# DM1092_TopLevel.net
KiCad netlist of a schematic drawn in Altium Designer
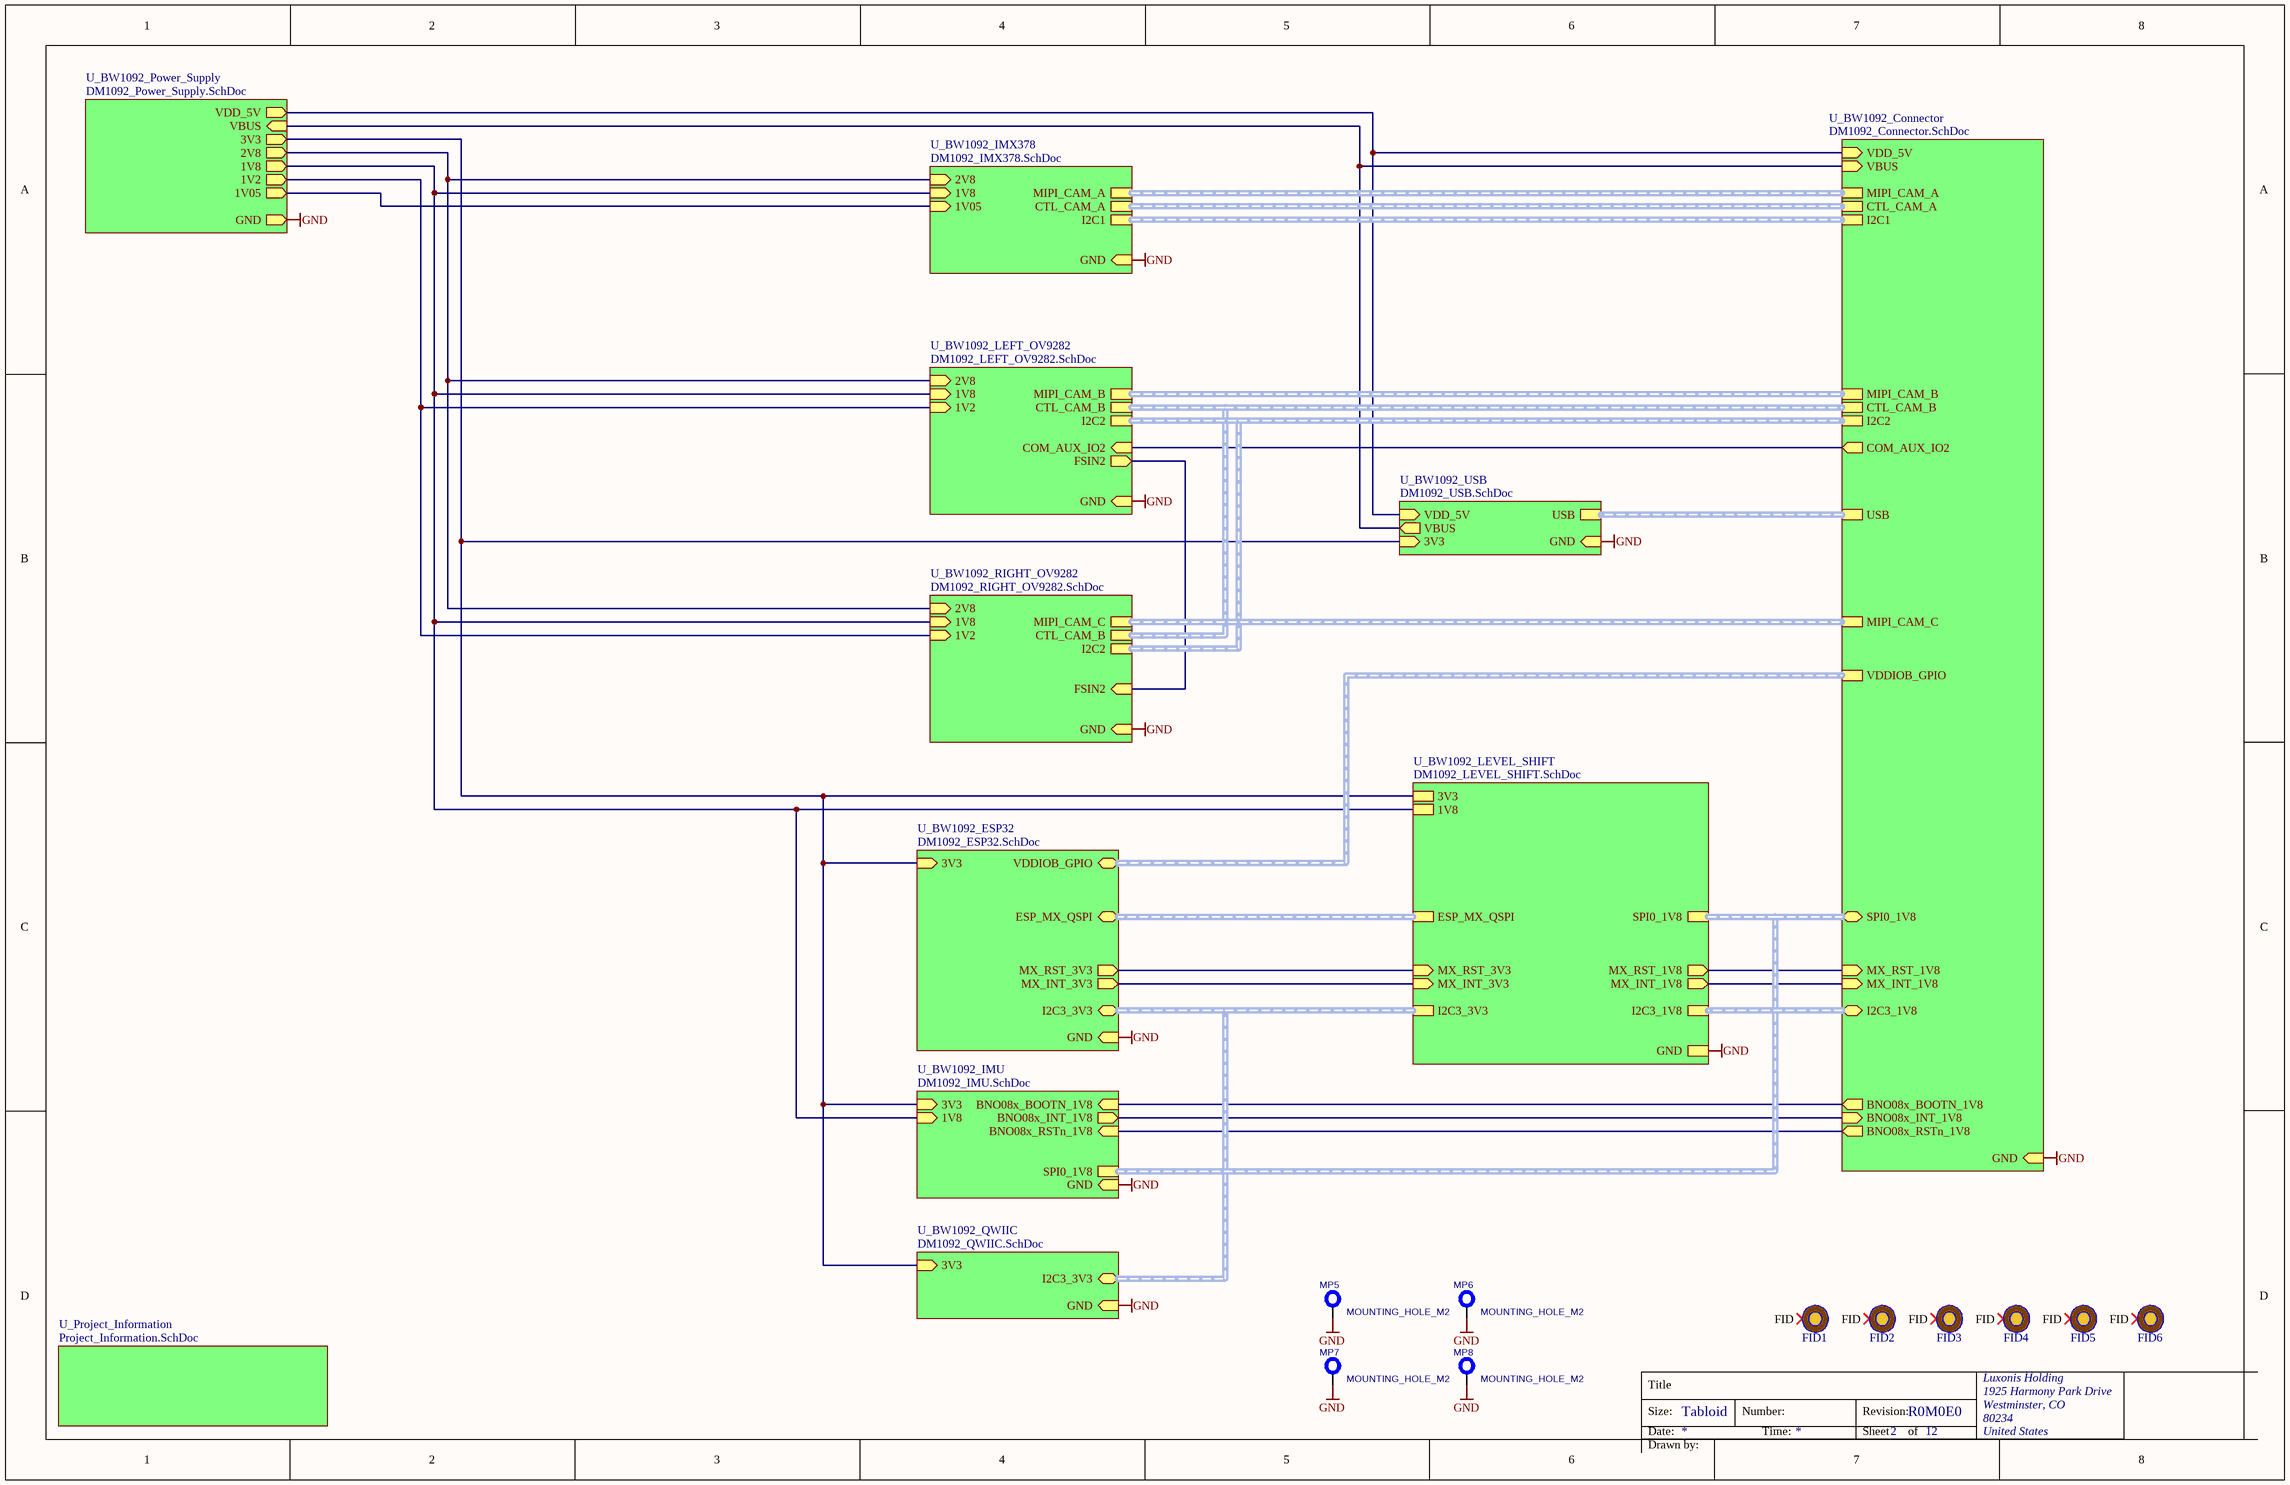
[diagram p0: DM1092_TopLevel.SchDoc]

(export (version "E")
  (design (tool "Eeschema 10.0.6"))
  (components
    (comp (ref "FID1")
      (value "FIDUCIAL_ROUND_1MM")
      (footprint "LuxonisMaster:FIDUCIAL_ROUND_1MM")
      (description "Fiducial with various available footprints")
      (libsource (lib "LuxonisMaster") (part "FIDUCIAL"))
    )
    (comp (ref "FID2")
      (value "FIDUCIAL_ROUND_1MM")
      (footprint "LuxonisMaster:FIDUCIAL_ROUND_1MM")
      (description "Fiducial with various available footprints")
      (libsource (lib "LuxonisMaster") (part "FIDUCIAL"))
    )
    (comp (ref "FID3")
      (value "FIDUCIAL_ROUND_1MM")
      (footprint "LuxonisMaster:FIDUCIAL_ROUND_1MM")
      (description "Fiducial with various available footprints")
      (libsource (lib "LuxonisMaster") (part "FIDUCIAL"))
    )
    (comp (ref "FID4")
      (value "FIDUCIAL_ROUND_1MM")
      (footprint "LuxonisMaster:FIDUCIAL_ROUND_1MM")
      (description "Fiducial with various available footprints")
      (libsource (lib "LuxonisMaster") (part "FIDUCIAL"))
    )
    (comp (ref "FID5")
      (value "FIDUCIAL_ROUND_1MM")
      (footprint "LuxonisMaster:FIDUCIAL_ROUND_1MM")
      (description "Fiducial with various available footprints")
      (libsource (lib "LuxonisMaster") (part "FIDUCIAL"))
    )
    (comp (ref "FID6")
      (value "FIDUCIAL_ROUND_1MM")
      (footprint "LuxonisMaster:FIDUCIAL_ROUND_1MM")
      (description "Fiducial with various available footprints")
      (libsource (lib "LuxonisMaster") (part "FIDUCIAL"))
    )
    (comp (ref "MP5")
      (value "MOUNTING_HOLE_M2")
      (footprint "LuxonisMaster:MOUNTING_HOLE_M2")
      (description "=CurrentFootprint")
      (libsource (lib "LuxonisMaster") (part "MP_Mounting-Holes"))
    )
    (comp (ref "MP6")
      (value "MOUNTING_HOLE_M2")
      (footprint "LuxonisMaster:MOUNTING_HOLE_M2")
      (description "=CurrentFootprint")
      (libsource (lib "LuxonisMaster") (part "MP_Mounting-Holes"))
    )
    (comp (ref "MP7")
      (value "MOUNTING_HOLE_M2")
      (footprint "LuxonisMaster:MOUNTING_HOLE_M2")
      (description "=CurrentFootprint")
      (libsource (lib "LuxonisMaster") (part "MP_Mounting-Holes"))
    )
    (comp (ref "MP8")
      (value "MOUNTING_HOLE_M2")
      (footprint "LuxonisMaster:MOUNTING_HOLE_M2")
      (description "=CurrentFootprint")
      (libsource (lib "LuxonisMaster") (part "MP_Mounting-Holes"))
    )
  )
  (nets
    (net (code "30") (name "GND") (class "Default")
      (node (ref "MP5") (pin "1") (pintype "passive"))
      (node (ref "MP6") (pin "1") (pintype "passive"))
      (node (ref "MP7") (pin "1") (pintype "passive"))
      (node (ref "MP8") (pin "1") (pintype "passive"))
    )
    (net (code "31") (name "unconnected-(FID1-PadFID)") (class "Default")
      (node (ref "FID1") (pin "FID") (pinfunction "FID_FID") (pintype "input+no_connect"))
    )
    (net (code "32") (name "unconnected-(FID2-PadFID)") (class "Default")
      (node (ref "FID2") (pin "FID") (pinfunction "FID_FID") (pintype "input+no_connect"))
    )
    (net (code "33") (name "unconnected-(FID3-PadFID)") (class "Default")
      (node (ref "FID3") (pin "FID") (pinfunction "FID_FID") (pintype "input+no_connect"))
    )
    (net (code "34") (name "unconnected-(FID4-PadFID)") (class "Default")
      (node (ref "FID4") (pin "FID") (pinfunction "FID_FID") (pintype "input+no_connect"))
    )
    (net (code "35") (name "unconnected-(FID5-PadFID)") (class "Default")
      (node (ref "FID5") (pin "FID") (pinfunction "FID_FID") (pintype "input+no_connect"))
    )
    (net (code "36") (name "unconnected-(FID6-PadFID)") (class "Default")
      (node (ref "FID6") (pin "FID") (pinfunction "FID_FID") (pintype "input+no_connect"))
    )
  )
)
